# RasPi-BplusHAT.net
KiCad netlist of a schematic drawn in EAGLE
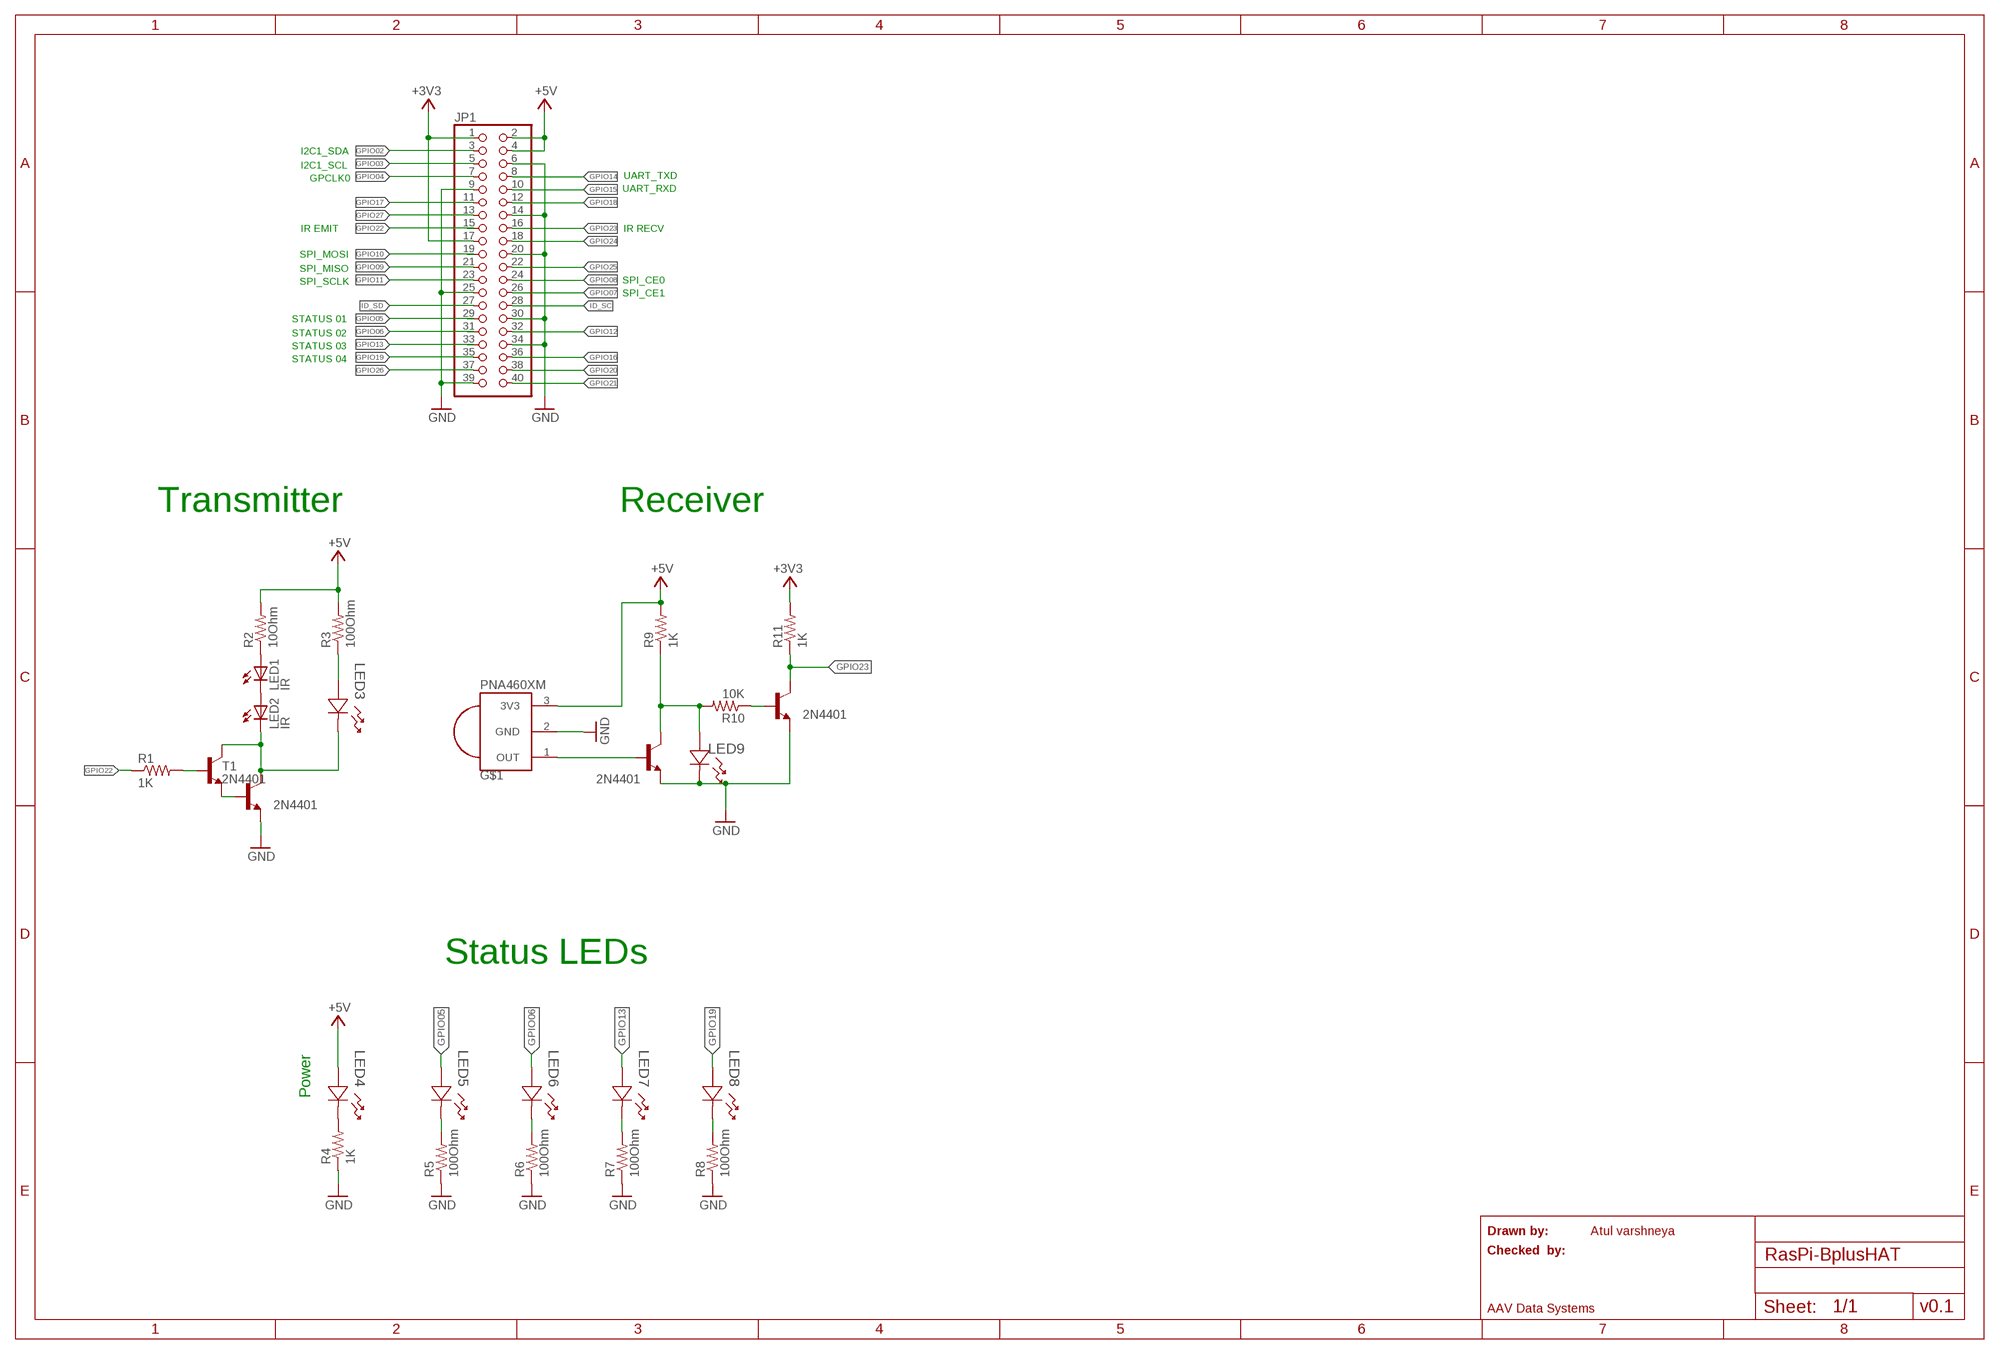
[diagram p0: schematic, sheet 1]

(export (version "E")
  (design (tool "Eeschema 10.0.6"))
  (components
    (comp (ref "G$1")
      (value "PNA460XM")
      (footprint "eagle-import:PNA460XM")
      (fields (field (name "MPN") "TSDP34138"))
      (libsource (lib "eagle-import") (part "PNA460XM"))
    )
    (comp (ref "JP1")
      (value "PINHD-2X20")
      (footprint "eagle-import:2X20")
      (libsource (lib "eagle-import") (part "PINHD-2X20"))
    )
    (comp (ref "LED1")
      (value "IR")
      (footprint "eagle-import:MICRO-SIDELED")
      (fields (field (name "MPN") "VSMB10940X01"))
      (libsource (lib "eagle-import") (part "LEDMICRO-SIDELED"))
    )
    (comp (ref "LED2")
      (value "IR")
      (footprint "eagle-import:MICRO-SIDELED")
      (fields (field (name "MPN") "VSMB10940X01"))
      (libsource (lib "eagle-import") (part "LEDMICRO-SIDELED"))
    )
    (comp (ref "LED3")
      (value "597-3401-407F")
      (footprint "eagle-import:LED_597-3401-407F")
      (libsource (lib "eagle-import") (part "597-3401-407F"))
    )
    (comp (ref "LED4")
      (value "597-3311-407F")
      (footprint "eagle-import:LED_597-3311-407F")
      (libsource (lib "eagle-import") (part "597-3311-407F"))
    )
    (comp (ref "LED5")
      (value "597-3311-407F")
      (footprint "eagle-import:LED_597-3311-407F")
      (libsource (lib "eagle-import") (part "597-3311-407F"))
    )
    (comp (ref "LED6")
      (value "597-3401-407F")
      (footprint "eagle-import:LED_597-3401-407F")
      (libsource (lib "eagle-import") (part "597-3401-407F"))
    )
    (comp (ref "LED7")
      (value "597-3111-407F")
      (footprint "eagle-import:LED_597-3111-407F")
      (libsource (lib "eagle-import") (part "597-3111-407F"))
    )
    (comp (ref "LED8")
      (value "597-3401-407F")
      (footprint "eagle-import:LED_597-3401-407F")
      (libsource (lib "eagle-import") (part "597-3401-407F"))
    )
    (comp (ref "LED9")
      (value "597-3401-407F")
      (footprint "eagle-import:LED_597-3401-407F")
      (libsource (lib "eagle-import") (part "597-3401-407F"))
    )
    (comp (ref "R1")
      (value "1K")
      (footprint "eagle-import:R2010")
      (fields (field (name "MF") "VISHAY/DALE") (field (name "MPN") "CRCW08051K00JNEA"))
      (libsource (lib "eagle-import") (part "R-US_R2010"))
    )
    (comp (ref "R2")
      (value "10Ohm")
      (footprint "eagle-import:R2010")
      (fields (field (name "MF") "OUTSOURCE ITEM") (field (name "MPN") "RP2012S-100-F"))
      (libsource (lib "eagle-import") (part "R-US_R2010"))
    )
    (comp (ref "R3")
      (value "100Ohm")
      (footprint "eagle-import:R2010")
      (fields (field (name "MPN") "CRCW0805100RJNTA"))
      (libsource (lib "eagle-import") (part "R-US_R2010"))
    )
    (comp (ref "R4")
      (value "1K")
      (footprint "eagle-import:R2010")
      (fields (field (name "MF") "VISHAY/DALE") (field (name "MPN") "CRCW08051K00JNEA"))
      (libsource (lib "eagle-import") (part "R-US_R2010"))
    )
    (comp (ref "R5")
      (value "100Ohm")
      (footprint "eagle-import:R2010")
      (fields (field (name "MPN") "CRCW0805100RJNTA"))
      (libsource (lib "eagle-import") (part "R-US_R2010"))
    )
    (comp (ref "R6")
      (value "100Ohm")
      (footprint "eagle-import:R2010")
      (fields (field (name "MPN") "CRCW0805100RJNTA"))
      (libsource (lib "eagle-import") (part "R-US_R2010"))
    )
    (comp (ref "R7")
      (value "100Ohm")
      (footprint "eagle-import:R2010")
      (fields (field (name "MPN") "CRCW0805100RJNTA"))
      (libsource (lib "eagle-import") (part "R-US_R2010"))
    )
    (comp (ref "R8")
      (value "100Ohm")
      (footprint "eagle-import:R2010")
      (fields (field (name "MPN") "CRCW0805100RJNTA"))
      (libsource (lib "eagle-import") (part "R-US_R2010"))
    )
    (comp (ref "R9")
      (value "1K")
      (footprint "eagle-import:R2010")
      (fields (field (name "MF") "VISHAY/DALE") (field (name "MPN") "CRCW08051K00JNEA"))
      (libsource (lib "eagle-import") (part "R-US_R2010"))
    )
    (comp (ref "R10")
      (value "10K")
      (footprint "eagle-import:R2010")
      (fields (field (name "MF") "VISHAY/DALE") (field (name "MPN") "CRCW080510K0JNEB"))
      (libsource (lib "eagle-import") (part "R-US_R2010"))
    )
    (comp (ref "R11")
      (value "1K")
      (footprint "eagle-import:R2010")
      (fields (field (name "MF") "VISHAY/DALE") (field (name "MPN") "CRCW08051K00JNEA"))
      (libsource (lib "eagle-import") (part "R-US_R2010"))
    )
    (comp (ref "T1")
      (value "2N4401")
      (footprint "eagle-import:SOT23-BEC")
      (fields (field (name "MPN") "MMBT4401-TP"))
      (libsource (lib "eagle-import") (part "transistor-neu-to92_-NPN-SOT23-BECMMBT4401LT1"))
    )
    (comp (ref "T2")
      (value "2N4401")
      (footprint "eagle-import:SOT23-BEC")
      (fields (field (name "MPN") "MMBT4401-TP"))
      (libsource (lib "eagle-import") (part "transistor-neu-to92_-NPN-SOT23-BECMMBT4401LT1"))
    )
    (comp (ref "T3")
      (value "2N4401")
      (footprint "eagle-import:SOT23-BEC")
      (fields (field (name "MPN") "MMBT4401-TP"))
      (libsource (lib "eagle-import") (part "-NPN-SOT23-BECMMBT4401LT1"))
    )
    (comp (ref "T4")
      (value "2N4401")
      (footprint "eagle-import:SOT23-BEC")
      (fields (field (name "MPN") "MMBT4401-TP"))
      (libsource (lib "eagle-import") (part "-NPN-SOT23-BECMMBT4401LT1"))
    )
  )
  (nets
    (net (code "1") (name "+3V3") (class "Default")
      (node (ref "JP1") (pin "1") (pinfunction "1_1") (pintype "passive"))
      (node (ref "JP1") (pin "17") (pinfunction "17_17") (pintype "passive"))
      (node (ref "R11") (pin "2") (pinfunction "2_2") (pintype "passive"))
    )
    (net (code "2") (name "+5V") (class "Default")
      (node (ref "G$1") (pin "3") (pinfunction "3V3_3") (pintype "power_in"))
      (node (ref "JP1") (pin "2") (pinfunction "2_2") (pintype "passive"))
      (node (ref "JP1") (pin "4") (pinfunction "4_4") (pintype "passive"))
      (node (ref "LED4") (pin "2") (pinfunction "2_2") (pintype "passive"))
      (node (ref "R2") (pin "2") (pinfunction "2_2") (pintype "passive"))
      (node (ref "R3") (pin "2") (pinfunction "2_2") (pintype "passive"))
      (node (ref "R9") (pin "2") (pinfunction "2_2") (pintype "passive"))
    )
    (net (code "3") (name "GND") (class "Default")
      (node (ref "G$1") (pin "2") (pinfunction "GND_2") (pintype "power_in"))
      (node (ref "JP1") (pin "14") (pinfunction "14_14") (pintype "passive"))
      (node (ref "JP1") (pin "20") (pinfunction "20_20") (pintype "passive"))
      (node (ref "JP1") (pin "25") (pinfunction "25_25") (pintype "passive"))
      (node (ref "JP1") (pin "30") (pinfunction "30_30") (pintype "passive"))
      (node (ref "JP1") (pin "34") (pinfunction "34_34") (pintype "passive"))
      (node (ref "JP1") (pin "39") (pinfunction "39_39") (pintype "passive"))
      (node (ref "JP1") (pin "6") (pinfunction "6_6") (pintype "passive"))
      (node (ref "JP1") (pin "9") (pinfunction "9_9") (pintype "passive"))
      (node (ref "LED9") (pin "1") (pinfunction "1_1") (pintype "passive"))
      (node (ref "R4") (pin "1") (pinfunction "1_1") (pintype "passive"))
      (node (ref "R5") (pin "1") (pinfunction "1_1") (pintype "passive"))
      (node (ref "R6") (pin "1") (pinfunction "1_1") (pintype "passive"))
      (node (ref "R7") (pin "1") (pinfunction "1_1") (pintype "passive"))
      (node (ref "R8") (pin "1") (pinfunction "1_1") (pintype "passive"))
      (node (ref "T2") (pin "E") (pinfunction "E_E") (pintype "passive"))
      (node (ref "T3") (pin "E") (pinfunction "E_E") (pintype "passive"))
      (node (ref "T4") (pin "E") (pinfunction "E_E") (pintype "passive"))
    )
    (net (code "4") (name "GPIO02") (class "Default")
      (node (ref "JP1") (pin "3") (pinfunction "3_3") (pintype "passive"))
    )
    (net (code "5") (name "GPIO03") (class "Default")
      (node (ref "JP1") (pin "5") (pinfunction "5_5") (pintype "passive"))
    )
    (net (code "6") (name "GPIO04") (class "Default")
      (node (ref "JP1") (pin "7") (pinfunction "7_7") (pintype "passive"))
    )
    (net (code "7") (name "GPIO05") (class "Default")
      (node (ref "JP1") (pin "29") (pinfunction "29_29") (pintype "passive"))
      (node (ref "LED5") (pin "2") (pinfunction "2_2") (pintype "passive"))
    )
    (net (code "8") (name "GPIO06") (class "Default")
      (node (ref "JP1") (pin "31") (pinfunction "31_31") (pintype "passive"))
      (node (ref "LED6") (pin "2") (pinfunction "2_2") (pintype "passive"))
    )
    (net (code "9") (name "GPIO07") (class "Default")
      (node (ref "JP1") (pin "26") (pinfunction "26_26") (pintype "passive"))
    )
    (net (code "10") (name "GPIO08") (class "Default")
      (node (ref "JP1") (pin "24") (pinfunction "24_24") (pintype "passive"))
    )
    (net (code "11") (name "GPIO09") (class "Default")
      (node (ref "JP1") (pin "21") (pinfunction "21_21") (pintype "passive"))
    )
    (net (code "12") (name "GPIO10") (class "Default")
      (node (ref "JP1") (pin "19") (pinfunction "19_19") (pintype "passive"))
    )
    (net (code "13") (name "GPIO11") (class "Default")
      (node (ref "JP1") (pin "23") (pinfunction "23_23") (pintype "passive"))
    )
    (net (code "14") (name "GPIO12") (class "Default")
      (node (ref "JP1") (pin "32") (pinfunction "32_32") (pintype "passive"))
    )
    (net (code "15") (name "GPIO13") (class "Default")
      (node (ref "JP1") (pin "33") (pinfunction "33_33") (pintype "passive"))
      (node (ref "LED7") (pin "2") (pinfunction "2_2") (pintype "passive"))
    )
    (net (code "16") (name "GPIO14") (class "Default")
      (node (ref "JP1") (pin "8") (pinfunction "8_8") (pintype "passive"))
    )
    (net (code "17") (name "GPIO15") (class "Default")
      (node (ref "JP1") (pin "10") (pinfunction "10_10") (pintype "passive"))
    )
    (net (code "18") (name "GPIO16") (class "Default")
      (node (ref "JP1") (pin "36") (pinfunction "36_36") (pintype "passive"))
    )
    (net (code "19") (name "GPIO17") (class "Default")
      (node (ref "JP1") (pin "11") (pinfunction "11_11") (pintype "passive"))
    )
    (net (code "20") (name "GPIO18") (class "Default")
      (node (ref "JP1") (pin "12") (pinfunction "12_12") (pintype "passive"))
    )
    (net (code "21") (name "GPIO19") (class "Default")
      (node (ref "JP1") (pin "35") (pinfunction "35_35") (pintype "passive"))
      (node (ref "LED8") (pin "2") (pinfunction "2_2") (pintype "passive"))
    )
    (net (code "22") (name "GPIO20") (class "Default")
      (node (ref "JP1") (pin "38") (pinfunction "38_38") (pintype "passive"))
    )
    (net (code "23") (name "GPIO21") (class "Default")
      (node (ref "JP1") (pin "40") (pinfunction "40_40") (pintype "passive"))
    )
    (net (code "24") (name "GPIO22") (class "Default")
      (node (ref "JP1") (pin "15") (pinfunction "15_15") (pintype "passive"))
      (node (ref "R1") (pin "1") (pinfunction "1_1") (pintype "passive"))
    )
    (net (code "25") (name "GPIO23") (class "Default")
      (node (ref "JP1") (pin "16") (pinfunction "16_16") (pintype "passive"))
      (node (ref "R11") (pin "1") (pinfunction "1_1") (pintype "passive"))
      (node (ref "T4") (pin "C") (pinfunction "C_C") (pintype "passive"))
    )
    (net (code "26") (name "GPIO24") (class "Default")
      (node (ref "JP1") (pin "18") (pinfunction "18_18") (pintype "passive"))
    )
    (net (code "27") (name "GPIO25") (class "Default")
      (node (ref "JP1") (pin "22") (pinfunction "22_22") (pintype "passive"))
    )
    (net (code "28") (name "GPIO26") (class "Default")
      (node (ref "JP1") (pin "37") (pinfunction "37_37") (pintype "passive"))
    )
    (net (code "29") (name "GPIO27") (class "Default")
      (node (ref "JP1") (pin "13") (pinfunction "13_13") (pintype "passive"))
    )
    (net (code "30") (name "ID_SC") (class "Default")
      (node (ref "JP1") (pin "28") (pinfunction "28_28") (pintype "passive"))
    )
    (net (code "31") (name "ID_SD") (class "Default")
      (node (ref "JP1") (pin "27") (pinfunction "27_27") (pintype "passive"))
    )
    (net (code "32") (name "Net-(G$1-OUT)") (class "Default")
      (node (ref "G$1") (pin "1") (pinfunction "OUT_1") (pintype "output"))
      (node (ref "T3") (pin "B") (pinfunction "B_B") (pintype "passive"))
    )
    (net (code "33") (name "Net-(LED1-PadA)") (class "Default")
      (node (ref "LED1") (pin "A") (pinfunction "A_A") (pintype "passive"))
      (node (ref "R2") (pin "1") (pinfunction "1_1") (pintype "passive"))
    )
    (net (code "34") (name "Net-(LED1-PadC)") (class "Default")
      (node (ref "LED1") (pin "C") (pinfunction "C_C") (pintype "passive"))
      (node (ref "LED2") (pin "A") (pinfunction "A_A") (pintype "passive"))
    )
    (net (code "35") (name "Net-(LED2-PadC)") (class "Default")
      (node (ref "LED2") (pin "C") (pinfunction "C_C") (pintype "passive"))
      (node (ref "LED3") (pin "1") (pinfunction "1_1") (pintype "passive"))
      (node (ref "T1") (pin "C") (pinfunction "C_C") (pintype "passive"))
      (node (ref "T2") (pin "C") (pinfunction "C_C") (pintype "passive"))
    )
    (net (code "36") (name "Net-(LED3-Pad2)") (class "Default")
      (node (ref "LED3") (pin "2") (pinfunction "2_2") (pintype "passive"))
      (node (ref "R3") (pin "1") (pinfunction "1_1") (pintype "passive"))
    )
    (net (code "37") (name "Net-(LED4-Pad1)") (class "Default")
      (node (ref "LED4") (pin "1") (pinfunction "1_1") (pintype "passive"))
      (node (ref "R4") (pin "2") (pinfunction "2_2") (pintype "passive"))
    )
    (net (code "38") (name "Net-(LED5-Pad1)") (class "Default")
      (node (ref "LED5") (pin "1") (pinfunction "1_1") (pintype "passive"))
      (node (ref "R5") (pin "2") (pinfunction "2_2") (pintype "passive"))
    )
    (net (code "39") (name "Net-(LED6-Pad1)") (class "Default")
      (node (ref "LED6") (pin "1") (pinfunction "1_1") (pintype "passive"))
      (node (ref "R6") (pin "2") (pinfunction "2_2") (pintype "passive"))
    )
    (net (code "40") (name "Net-(LED7-Pad1)") (class "Default")
      (node (ref "LED7") (pin "1") (pinfunction "1_1") (pintype "passive"))
      (node (ref "R7") (pin "2") (pinfunction "2_2") (pintype "passive"))
    )
    (net (code "41") (name "Net-(LED8-Pad1)") (class "Default")
      (node (ref "LED8") (pin "1") (pinfunction "1_1") (pintype "passive"))
      (node (ref "R8") (pin "2") (pinfunction "2_2") (pintype "passive"))
    )
    (net (code "42") (name "Net-(LED9-Pad2)") (class "Default")
      (node (ref "LED9") (pin "2") (pinfunction "2_2") (pintype "passive"))
      (node (ref "R10") (pin "2") (pinfunction "2_2") (pintype "passive"))
      (node (ref "R9") (pin "1") (pinfunction "1_1") (pintype "passive"))
      (node (ref "T3") (pin "C") (pinfunction "C_C") (pintype "passive"))
    )
    (net (code "43") (name "Net-(R1-Pad2)") (class "Default")
      (node (ref "R1") (pin "2") (pinfunction "2_2") (pintype "passive"))
      (node (ref "T1") (pin "B") (pinfunction "B_B") (pintype "passive"))
    )
    (net (code "44") (name "Net-(R10-Pad1)") (class "Default")
      (node (ref "R10") (pin "1") (pinfunction "1_1") (pintype "passive"))
      (node (ref "T4") (pin "B") (pinfunction "B_B") (pintype "passive"))
    )
    (net (code "45") (name "Net-(T1-PadE)") (class "Default")
      (node (ref "T1") (pin "E") (pinfunction "E_E") (pintype "passive"))
      (node (ref "T2") (pin "B") (pinfunction "B_B") (pintype "passive"))
    )
  )
)
